# schematic.net
KiCad netlist of a schematic drawn in EAGLE
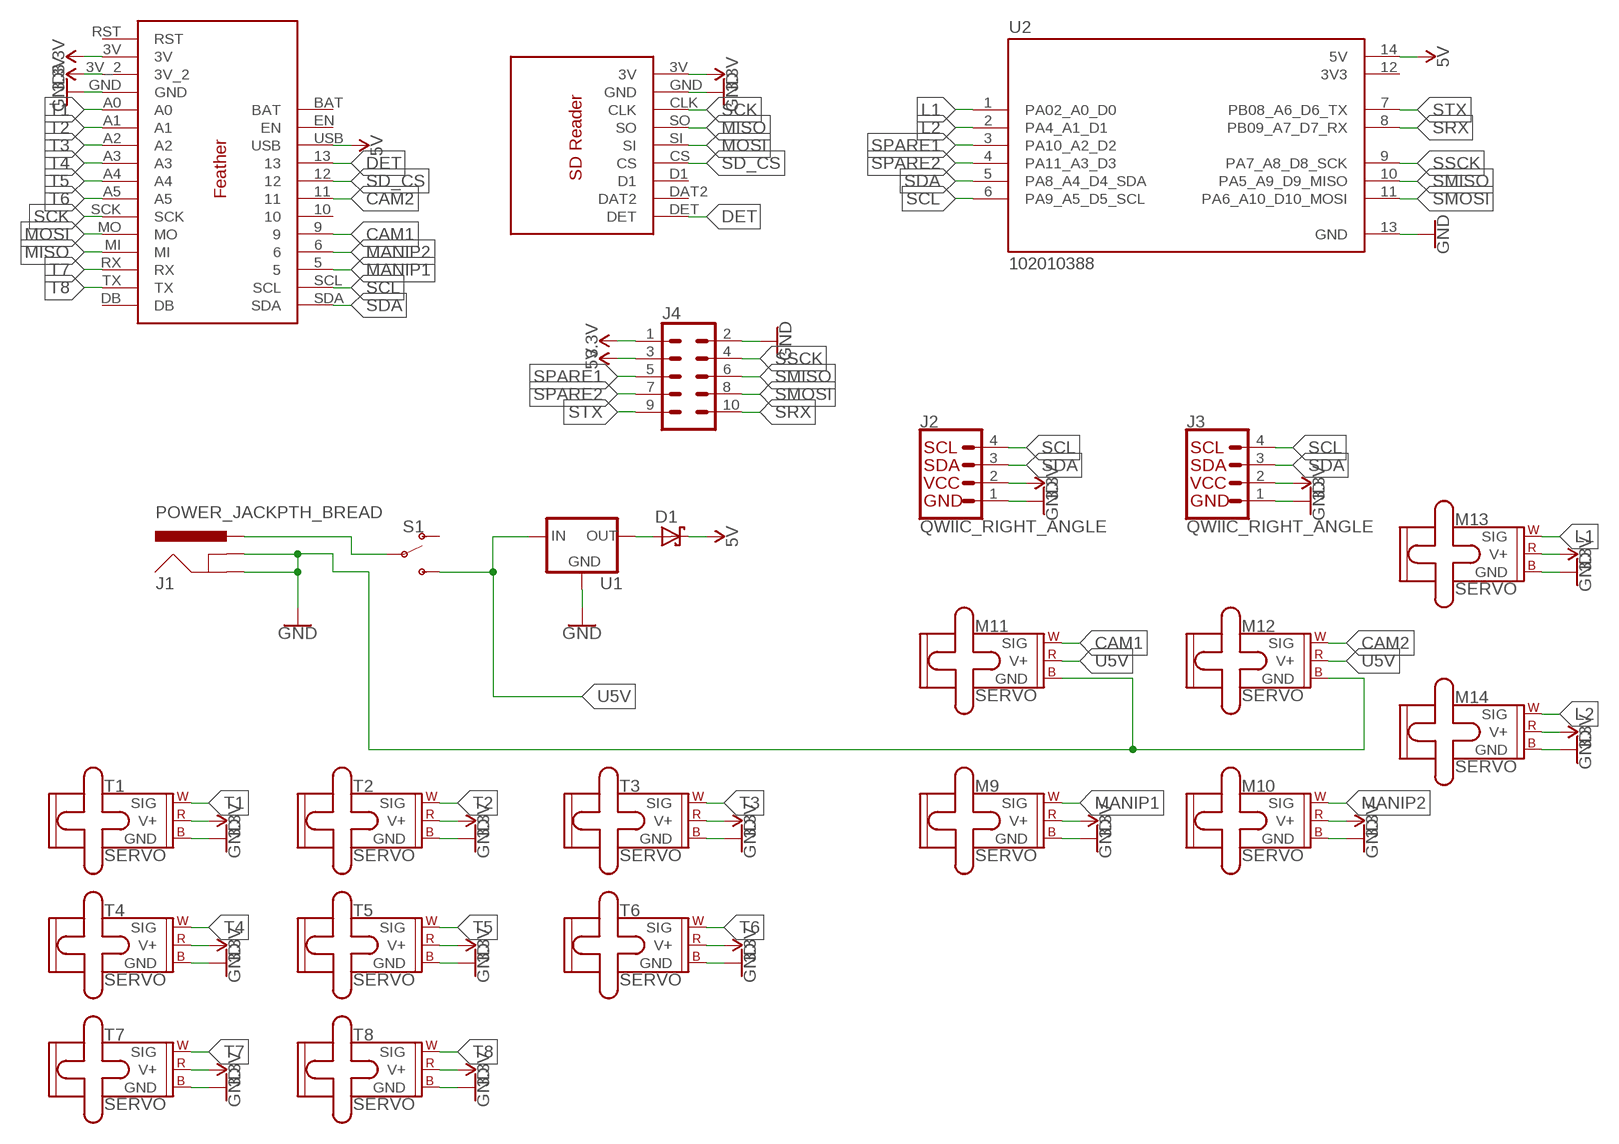
[diagram p0: schematic, sheet 1]

(export (version "E")
  (design (tool "Eeschema 10.0.6"))
  (components
    (comp (ref "D1")
      (value "SCHOTTKY-DIODEDO41")
      (footprint "eagle-import:DO41-10")
      (libsource (lib "eagle-import") (part "SCHOTTKY-DIODEDO41"))
    )
    (comp (ref "J1")
      (value "POWER_JACKPTH_BREAD")
      (footprint "eagle-import:POWER_JACK_PTH_BREAD")
      (libsource (lib "eagle-import") (part "POWER_JACKPTH_BREAD"))
    )
    (comp (ref "J2")
      (value "QWIIC_RIGHT_ANGLE")
      (footprint "eagle-import:JST04_1MM_RA")
      (libsource (lib "eagle-import") (part "QWIIC_CONNECTORJS-1MM"))
    )
    (comp (ref "J3")
      (value "QWIIC_RIGHT_ANGLE")
      (footprint "eagle-import:JST04_1MM_RA")
      (libsource (lib "eagle-import") (part "QWIIC_CONNECTORJS-1MM"))
    )
    (comp (ref "J4")
      (value "CONN_05X2PTH")
      (footprint "eagle-import:2X5")
      (libsource (lib "eagle-import") (part "CONN_05X2PTH"))
    )
    (comp (ref "M9")
      (value "SERVO")
      (footprint "eagle-import:1X03")
      (libsource (lib "eagle-import") (part "SERVO"))
    )
    (comp (ref "M10")
      (value "SERVO")
      (footprint "eagle-import:1X03")
      (libsource (lib "eagle-import") (part "SERVO"))
    )
    (comp (ref "M11")
      (value "SERVO")
      (footprint "eagle-import:1X03")
      (libsource (lib "eagle-import") (part "SERVO"))
    )
    (comp (ref "M12")
      (value "SERVO")
      (footprint "eagle-import:1X03")
      (libsource (lib "eagle-import") (part "SERVO"))
    )
    (comp (ref "M13")
      (value "SERVO")
      (footprint "eagle-import:1X03")
      (libsource (lib "eagle-import") (part "SERVO"))
    )
    (comp (ref "M14")
      (value "SERVO")
      (footprint "eagle-import:1X03")
      (libsource (lib "eagle-import") (part "SERVO"))
    )
    (comp (ref "S1")
      (value "SWITCH-SPDT-PTH-11.6X4.0MM")
      (footprint "eagle-import:SWITCH_SPDT_PTH_11.6X4.0MM")
      (libsource (lib "eagle-import") (part "SWITCH-SPDT-PTH-11.6X4.0MM"))
    )
    (comp (ref "T1")
      (value "SERVO")
      (footprint "eagle-import:1X03")
      (libsource (lib "eagle-import") (part "SERVO"))
    )
    (comp (ref "T2")
      (value "SERVO")
      (footprint "eagle-import:1X03")
      (libsource (lib "eagle-import") (part "SERVO"))
    )
    (comp (ref "T3")
      (value "SERVO")
      (footprint "eagle-import:1X03")
      (libsource (lib "eagle-import") (part "SERVO"))
    )
    (comp (ref "T4")
      (value "SERVO")
      (footprint "eagle-import:1X03")
      (libsource (lib "eagle-import") (part "SERVO"))
    )
    (comp (ref "T5")
      (value "SERVO")
      (footprint "eagle-import:1X03")
      (libsource (lib "eagle-import") (part "SERVO"))
    )
    (comp (ref "T6")
      (value "SERVO")
      (footprint "eagle-import:1X03")
      (libsource (lib "eagle-import") (part "SERVO"))
    )
    (comp (ref "T7")
      (value "SERVO")
      (footprint "eagle-import:1X03")
      (libsource (lib "eagle-import") (part "SERVO"))
    )
    (comp (ref "T8")
      (value "SERVO")
      (footprint "eagle-import:1X03")
      (libsource (lib "eagle-import") (part "SERVO"))
    )
    (comp (ref "U$1")
      (value "FEATHER")
      (footprint "eagle-import:FEATHER")
      (libsource (lib "eagle-import") (part "FEATHER"))
    )
    (comp (ref "U$3") (value "SD") (footprint "eagle-import:SD") (libsource (lib "eagle-import") (part "SD")))
    (comp (ref "U1")
      (value "V_REG_78XXSIDE")
      (footprint "eagle-import:78XXL")
      (libsource (lib "eagle-import") (part "V_REG_78XXSIDE"))
    )
    (comp (ref "U2")
      (value "102010388")
      (footprint "eagle-import:MODULE_102010388")
      (fields (field (name "MF") "Seeed Technology Co., Ltd"))
      (libsource (lib "eagle-import") (part "102010388"))
    )
  )
  (nets
    (net (code "1") (name "/3V3") (class "Default")
      (node (ref "U2") (pin "12") (pinfunction "3V3_12") (pintype "power_in"))
    )
    (net (code "2") (name "3.3V") (class "Default")
      (node (ref "J2") (pin "2") (pinfunction "2_2") (pintype "power_in"))
      (node (ref "J3") (pin "2") (pinfunction "2_2") (pintype "power_in"))
      (node (ref "J4") (pin "1") (pinfunction "1_1") (pintype "passive"))
      (node (ref "M10") (pin "2") (pinfunction "V+_2") (pintype "bidirectional"))
      (node (ref "M13") (pin "2") (pinfunction "V+_2") (pintype "bidirectional"))
      (node (ref "M14") (pin "2") (pinfunction "V+_2") (pintype "bidirectional"))
      (node (ref "M9") (pin "2") (pinfunction "V+_2") (pintype "bidirectional"))
      (node (ref "T1") (pin "2") (pinfunction "V+_2") (pintype "bidirectional"))
      (node (ref "T2") (pin "2") (pinfunction "V+_2") (pintype "bidirectional"))
      (node (ref "T3") (pin "2") (pinfunction "V+_2") (pintype "bidirectional"))
      (node (ref "T4") (pin "2") (pinfunction "V+_2") (pintype "bidirectional"))
      (node (ref "T5") (pin "2") (pinfunction "V+_2") (pintype "bidirectional"))
      (node (ref "T6") (pin "2") (pinfunction "V+_2") (pintype "bidirectional"))
      (node (ref "T7") (pin "2") (pinfunction "V+_2") (pintype "bidirectional"))
      (node (ref "T8") (pin "2") (pinfunction "V+_2") (pintype "bidirectional"))
      (node (ref "U$1") (pin "3V") (pinfunction "3V_3V") (pintype "bidirectional"))
      (node (ref "U$1") (pin "3V_2") (pinfunction "3V_2_3V_2") (pintype "bidirectional"))
      (node (ref "U$3") (pin "3V") (pinfunction "3V_3V") (pintype "bidirectional"))
    )
    (net (code "3") (name "5V") (class "Default")
      (node (ref "D1") (pin "C") (pinfunction "C_C") (pintype "passive"))
      (node (ref "J4") (pin "3") (pinfunction "3_3") (pintype "passive"))
      (node (ref "U$1") (pin "USB") (pinfunction "USB_USB") (pintype "bidirectional"))
      (node (ref "U2") (pin "14") (pinfunction "5V_14") (pintype "power_in"))
    )
    (net (code "4") (name "CAM1") (class "Default")
      (node (ref "M11") (pin "1") (pinfunction "SIG_1") (pintype "bidirectional"))
      (node (ref "U$1") (pin "9") (pinfunction "9_9") (pintype "bidirectional"))
    )
    (net (code "5") (name "CAM2") (class "Default")
      (node (ref "M12") (pin "1") (pinfunction "SIG_1") (pintype "bidirectional"))
      (node (ref "U$1") (pin "11") (pinfunction "11_11") (pintype "bidirectional"))
    )
    (net (code "6") (name "DET") (class "Default")
      (node (ref "U$1") (pin "13") (pinfunction "13_13") (pintype "bidirectional"))
      (node (ref "U$3") (pin "DET") (pinfunction "DET_DET") (pintype "bidirectional"))
    )
    (net (code "7") (name "GND") (class "Default")
      (node (ref "J1") (pin "GND") (pinfunction "GND_GND") (pintype "bidirectional"))
      (node (ref "J1") (pin "GNDBREAK") (pinfunction "GNDBREAK_GNDBREAK") (pintype "bidirectional"))
      (node (ref "J2") (pin "1") (pinfunction "1_1") (pintype "power_in"))
      (node (ref "J3") (pin "1") (pinfunction "1_1") (pintype "power_in"))
      (node (ref "J4") (pin "2") (pinfunction "2_2") (pintype "passive"))
      (node (ref "M10") (pin "3") (pinfunction "GND_3") (pintype "bidirectional"))
      (node (ref "M11") (pin "3") (pinfunction "GND_3") (pintype "bidirectional"))
      (node (ref "M12") (pin "3") (pinfunction "GND_3") (pintype "bidirectional"))
      (node (ref "M13") (pin "3") (pinfunction "GND_3") (pintype "bidirectional"))
      (node (ref "M14") (pin "3") (pinfunction "GND_3") (pintype "bidirectional"))
      (node (ref "M9") (pin "3") (pinfunction "GND_3") (pintype "bidirectional"))
      (node (ref "T1") (pin "3") (pinfunction "GND_3") (pintype "bidirectional"))
      (node (ref "T2") (pin "3") (pinfunction "GND_3") (pintype "bidirectional"))
      (node (ref "T3") (pin "3") (pinfunction "GND_3") (pintype "bidirectional"))
      (node (ref "T4") (pin "3") (pinfunction "GND_3") (pintype "bidirectional"))
      (node (ref "T5") (pin "3") (pinfunction "GND_3") (pintype "bidirectional"))
      (node (ref "T6") (pin "3") (pinfunction "GND_3") (pintype "bidirectional"))
      (node (ref "T7") (pin "3") (pinfunction "GND_3") (pintype "bidirectional"))
      (node (ref "T8") (pin "3") (pinfunction "GND_3") (pintype "bidirectional"))
      (node (ref "U$1") (pin "GND") (pinfunction "GND_GND") (pintype "bidirectional"))
      (node (ref "U$3") (pin "GND") (pinfunction "GND_GND") (pintype "bidirectional"))
      (node (ref "U1") (pin "GND") (pinfunction "GND_GND") (pintype "input"))
      (node (ref "U2") (pin "13") (pinfunction "GND_13") (pintype "power_in"))
    )
    (net (code "8") (name "L1") (class "Default")
      (node (ref "M13") (pin "1") (pinfunction "SIG_1") (pintype "bidirectional"))
      (node (ref "U2") (pin "1") (pinfunction "PA02_A0_D0_1") (pintype "bidirectional"))
    )
    (net (code "9") (name "L2") (class "Default")
      (node (ref "M14") (pin "1") (pinfunction "SIG_1") (pintype "bidirectional"))
      (node (ref "U2") (pin "2") (pinfunction "PA4_A1_D1_2") (pintype "bidirectional"))
    )
    (net (code "10") (name "MANIP1") (class "Default")
      (node (ref "M9") (pin "1") (pinfunction "SIG_1") (pintype "bidirectional"))
      (node (ref "U$1") (pin "5") (pinfunction "5_5") (pintype "bidirectional"))
    )
    (net (code "11") (name "MANIP2") (class "Default")
      (node (ref "M10") (pin "1") (pinfunction "SIG_1") (pintype "bidirectional"))
      (node (ref "U$1") (pin "6") (pinfunction "6_6") (pintype "bidirectional"))
    )
    (net (code "12") (name "MISO") (class "Default")
      (node (ref "U$1") (pin "MI") (pinfunction "MI_MI") (pintype "bidirectional"))
      (node (ref "U$3") (pin "SO") (pinfunction "SO_SO") (pintype "bidirectional"))
    )
    (net (code "13") (name "MOSI") (class "Default")
      (node (ref "U$1") (pin "MO") (pinfunction "MO_MO") (pintype "bidirectional"))
      (node (ref "U$3") (pin "SI") (pinfunction "SI_SI") (pintype "bidirectional"))
    )
    (net (code "14") (name "Net-(D1-PadA)") (class "Default")
      (node (ref "D1") (pin "A") (pinfunction "A_A") (pintype "passive"))
      (node (ref "U1") (pin "OUT") (pinfunction "OUT_OUT") (pintype "passive"))
    )
    (net (code "15") (name "Net-(S1-P)") (class "Default")
      (node (ref "J1") (pin "PWR") (pinfunction "PWR_PWR") (pintype "bidirectional"))
      (node (ref "S1") (pin "2") (pinfunction "P_2") (pintype "passive"))
    )
    (net (code "16") (name "SCK") (class "Default")
      (node (ref "U$1") (pin "SCK") (pinfunction "SCK_SCK") (pintype "bidirectional"))
      (node (ref "U$3") (pin "CLK") (pinfunction "CLK_CLK") (pintype "bidirectional"))
    )
    (net (code "17") (name "SCL") (class "Default")
      (node (ref "J2") (pin "4") (pinfunction "4_4") (pintype "passive"))
      (node (ref "J3") (pin "4") (pinfunction "4_4") (pintype "passive"))
      (node (ref "U$1") (pin "SCL") (pinfunction "SCL_SCL") (pintype "bidirectional"))
      (node (ref "U2") (pin "6") (pinfunction "PA9_A5_D5_SCL_6") (pintype "bidirectional"))
    )
    (net (code "18") (name "SDA") (class "Default")
      (node (ref "J2") (pin "3") (pinfunction "3_3") (pintype "passive"))
      (node (ref "J3") (pin "3") (pinfunction "3_3") (pintype "passive"))
      (node (ref "U$1") (pin "SDA") (pinfunction "SDA_SDA") (pintype "bidirectional"))
      (node (ref "U2") (pin "5") (pinfunction "PA8_A4_D4_SDA_5") (pintype "bidirectional"))
    )
    (net (code "19") (name "SD_CS") (class "Default")
      (node (ref "U$1") (pin "12") (pinfunction "12_12") (pintype "bidirectional"))
      (node (ref "U$3") (pin "CS") (pinfunction "CS_CS") (pintype "bidirectional"))
    )
    (net (code "20") (name "SMISO") (class "Default")
      (node (ref "J4") (pin "6") (pinfunction "6_6") (pintype "passive"))
      (node (ref "U2") (pin "10") (pinfunction "PA5_A9_D9_MISO_10") (pintype "bidirectional"))
    )
    (net (code "21") (name "SMOSI") (class "Default")
      (node (ref "J4") (pin "8") (pinfunction "8_8") (pintype "passive"))
      (node (ref "U2") (pin "11") (pinfunction "PA6_A10_D10_MOSI_11") (pintype "bidirectional"))
    )
    (net (code "22") (name "SPARE1") (class "Default")
      (node (ref "J4") (pin "5") (pinfunction "5_5") (pintype "passive"))
      (node (ref "U2") (pin "3") (pinfunction "PA10_A2_D2_3") (pintype "bidirectional"))
    )
    (net (code "23") (name "SPARE2") (class "Default")
      (node (ref "J4") (pin "7") (pinfunction "7_7") (pintype "passive"))
      (node (ref "U2") (pin "4") (pinfunction "PA11_A3_D3_4") (pintype "bidirectional"))
    )
    (net (code "24") (name "SRX") (class "Default")
      (node (ref "J4") (pin "10") (pinfunction "10_10") (pintype "passive"))
      (node (ref "U2") (pin "8") (pinfunction "PB09_A7_D7_RX_8") (pintype "bidirectional"))
    )
    (net (code "25") (name "SSCK") (class "Default")
      (node (ref "J4") (pin "4") (pinfunction "4_4") (pintype "passive"))
      (node (ref "U2") (pin "9") (pinfunction "PA7_A8_D8_SCK_9") (pintype "bidirectional"))
    )
    (net (code "26") (name "STX") (class "Default")
      (node (ref "J4") (pin "9") (pinfunction "9_9") (pintype "passive"))
      (node (ref "U2") (pin "7") (pinfunction "PB08_A6_D6_TX_7") (pintype "bidirectional"))
    )
    (net (code "27") (name "T1") (class "Default")
      (node (ref "T1") (pin "1") (pinfunction "SIG_1") (pintype "bidirectional"))
      (node (ref "U$1") (pin "A0") (pinfunction "A0_A0") (pintype "bidirectional"))
    )
    (net (code "28") (name "T2") (class "Default")
      (node (ref "T2") (pin "1") (pinfunction "SIG_1") (pintype "bidirectional"))
      (node (ref "U$1") (pin "A1") (pinfunction "A1_A1") (pintype "bidirectional"))
    )
    (net (code "29") (name "T3") (class "Default")
      (node (ref "T3") (pin "1") (pinfunction "SIG_1") (pintype "bidirectional"))
      (node (ref "U$1") (pin "A2") (pinfunction "A2_A2") (pintype "bidirectional"))
    )
    (net (code "30") (name "T4") (class "Default")
      (node (ref "T4") (pin "1") (pinfunction "SIG_1") (pintype "bidirectional"))
      (node (ref "U$1") (pin "A3") (pinfunction "A3_A3") (pintype "bidirectional"))
    )
    (net (code "31") (name "T5") (class "Default")
      (node (ref "T5") (pin "1") (pinfunction "SIG_1") (pintype "bidirectional"))
      (node (ref "U$1") (pin "A4") (pinfunction "A4_A4") (pintype "bidirectional"))
    )
    (net (code "32") (name "T6") (class "Default")
      (node (ref "T6") (pin "1") (pinfunction "SIG_1") (pintype "bidirectional"))
      (node (ref "U$1") (pin "A5") (pinfunction "A5_A5") (pintype "bidirectional"))
    )
    (net (code "33") (name "T7") (class "Default")
      (node (ref "T7") (pin "1") (pinfunction "SIG_1") (pintype "bidirectional"))
      (node (ref "U$1") (pin "RX") (pinfunction "RX_RX") (pintype "bidirectional"))
    )
    (net (code "34") (name "T8") (class "Default")
      (node (ref "T8") (pin "1") (pinfunction "SIG_1") (pintype "bidirectional"))
      (node (ref "U$1") (pin "TX") (pinfunction "TX_TX") (pintype "bidirectional"))
    )
    (net (code "35") (name "U5V") (class "Default")
      (node (ref "M11") (pin "2") (pinfunction "V+_2") (pintype "bidirectional"))
      (node (ref "M12") (pin "2") (pinfunction "V+_2") (pintype "bidirectional"))
      (node (ref "S1") (pin "3") (pinfunction "S_3") (pintype "passive"))
      (node (ref "U1") (pin "IN") (pinfunction "IN_IN") (pintype "input"))
    )
    (net (code "36") (name "unconnected-(S1-O-Pad1)") (class "Default")
      (node (ref "S1") (pin "1") (pinfunction "O_1") (pintype "passive"))
    )
    (net (code "37") (name "unconnected-(U$1-Pad10)") (class "Default")
      (node (ref "U$1") (pin "10") (pinfunction "10_10") (pintype "bidirectional"))
    )
    (net (code "38") (name "unconnected-(U$1-PadBAT)") (class "Default")
      (node (ref "U$1") (pin "BAT") (pinfunction "BAT_BAT") (pintype "bidirectional"))
    )
    (net (code "39") (name "unconnected-(U$1-PadDB)") (class "Default")
      (node (ref "U$1") (pin "DB") (pinfunction "DB_DB") (pintype "bidirectional"))
    )
    (net (code "40") (name "unconnected-(U$1-PadEN)") (class "Default")
      (node (ref "U$1") (pin "EN") (pinfunction "EN_EN") (pintype "bidirectional"))
    )
    (net (code "41") (name "unconnected-(U$1-PadRST)") (class "Default")
      (node (ref "U$1") (pin "RST") (pinfunction "RST_RST") (pintype "bidirectional"))
    )
    (net (code "42") (name "unconnected-(U$3-PadD1)") (class "Default")
      (node (ref "U$3") (pin "D1") (pinfunction "D1_D1") (pintype "bidirectional"))
    )
    (net (code "43") (name "unconnected-(U$3-PadDAT2)") (class "Default")
      (node (ref "U$3") (pin "DAT2") (pinfunction "DAT2_DAT2") (pintype "bidirectional"))
    )
  )
)
